# frankfurt_eth_pic.net
KiCad netlist of a schematic drawn in EAGLE
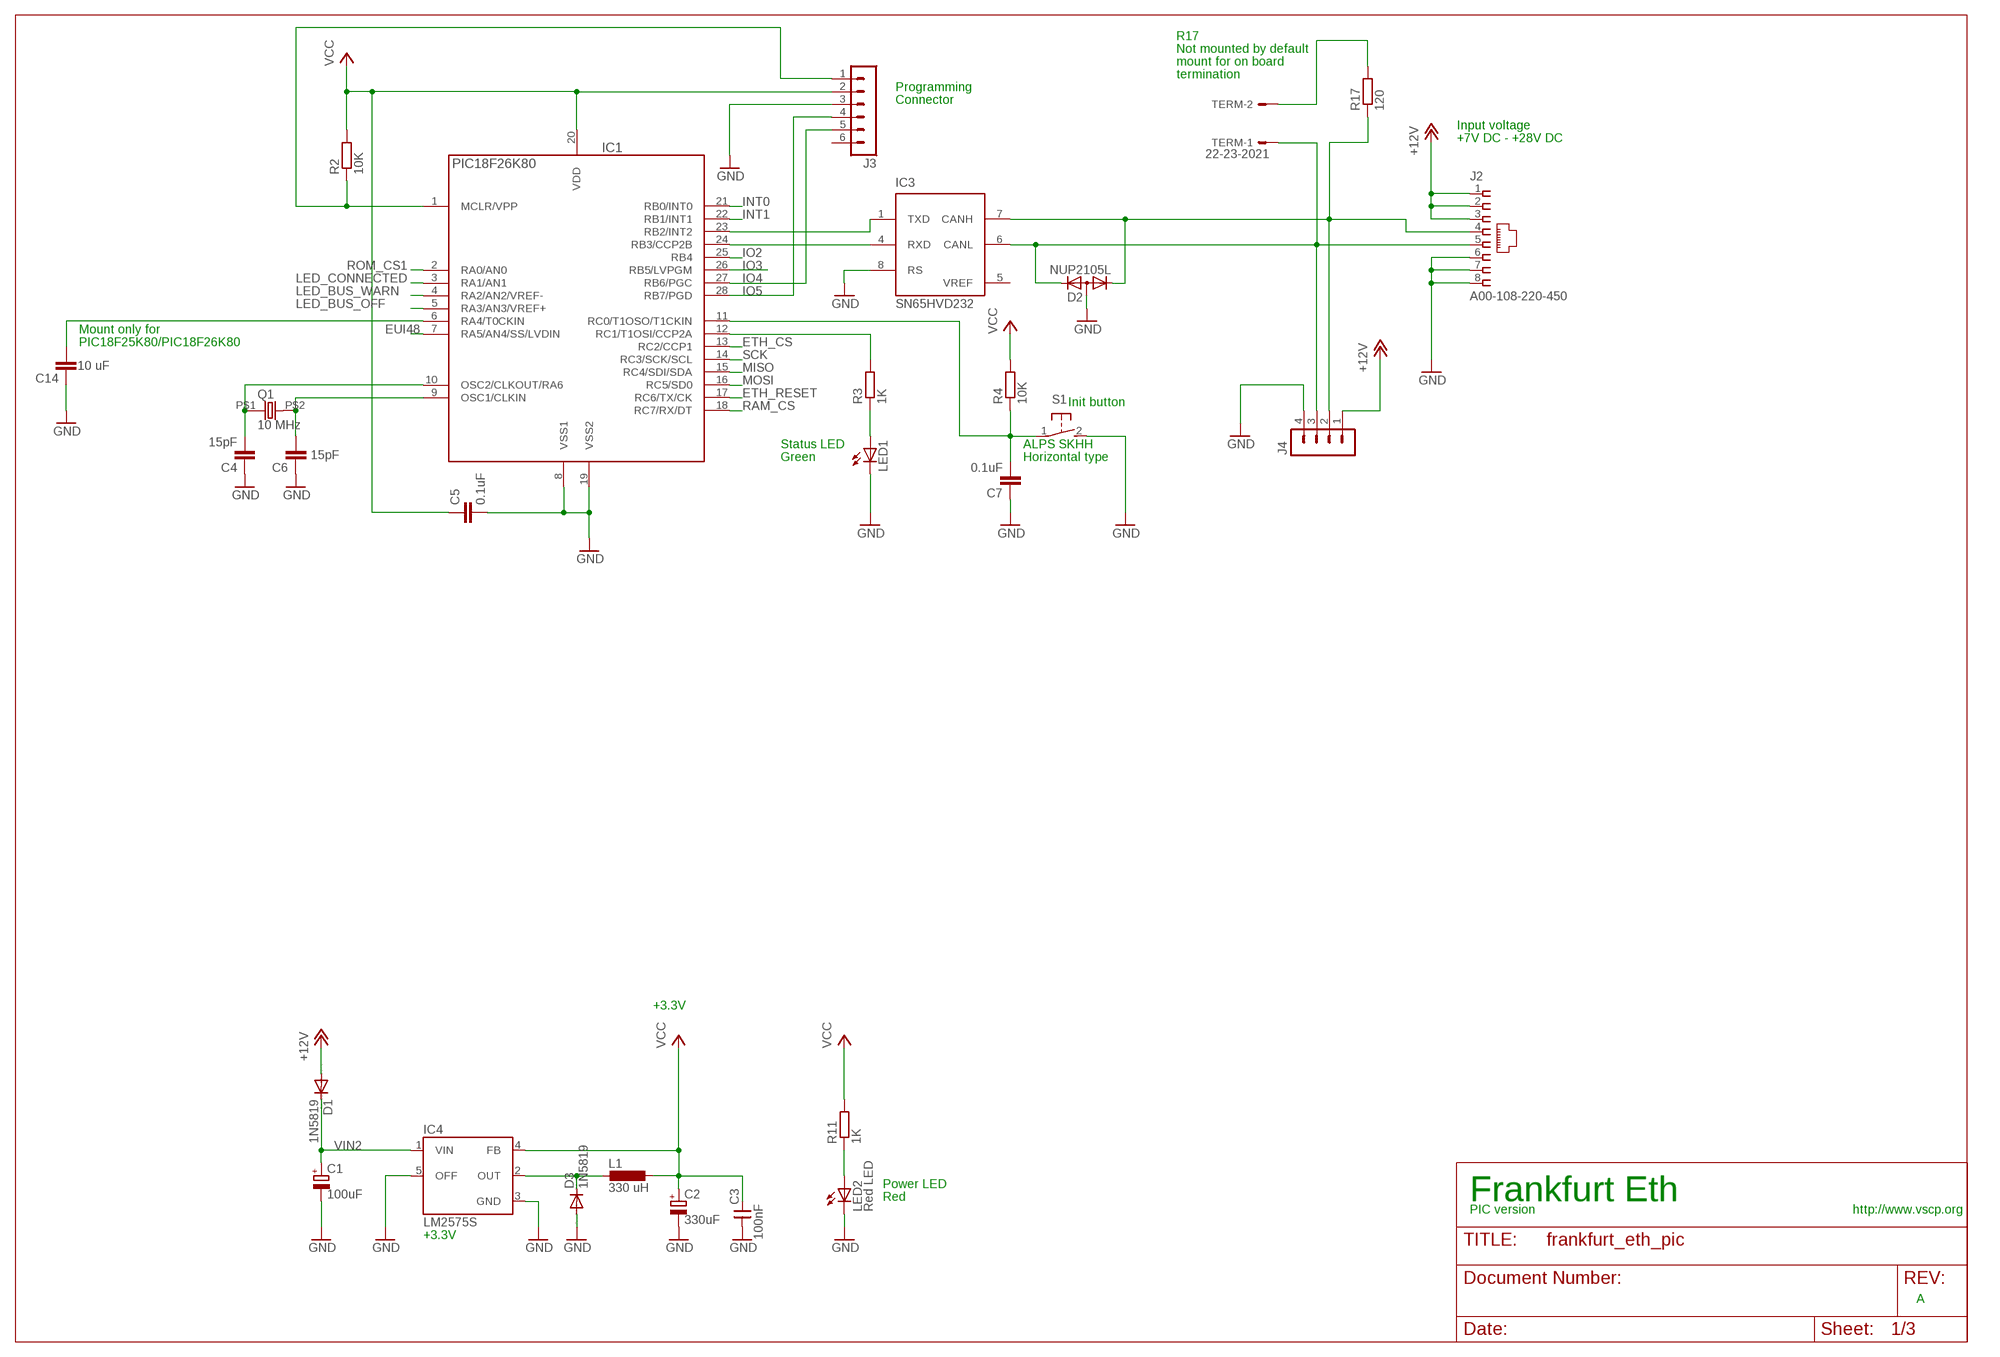
[diagram p0: schematic, sheet 1]
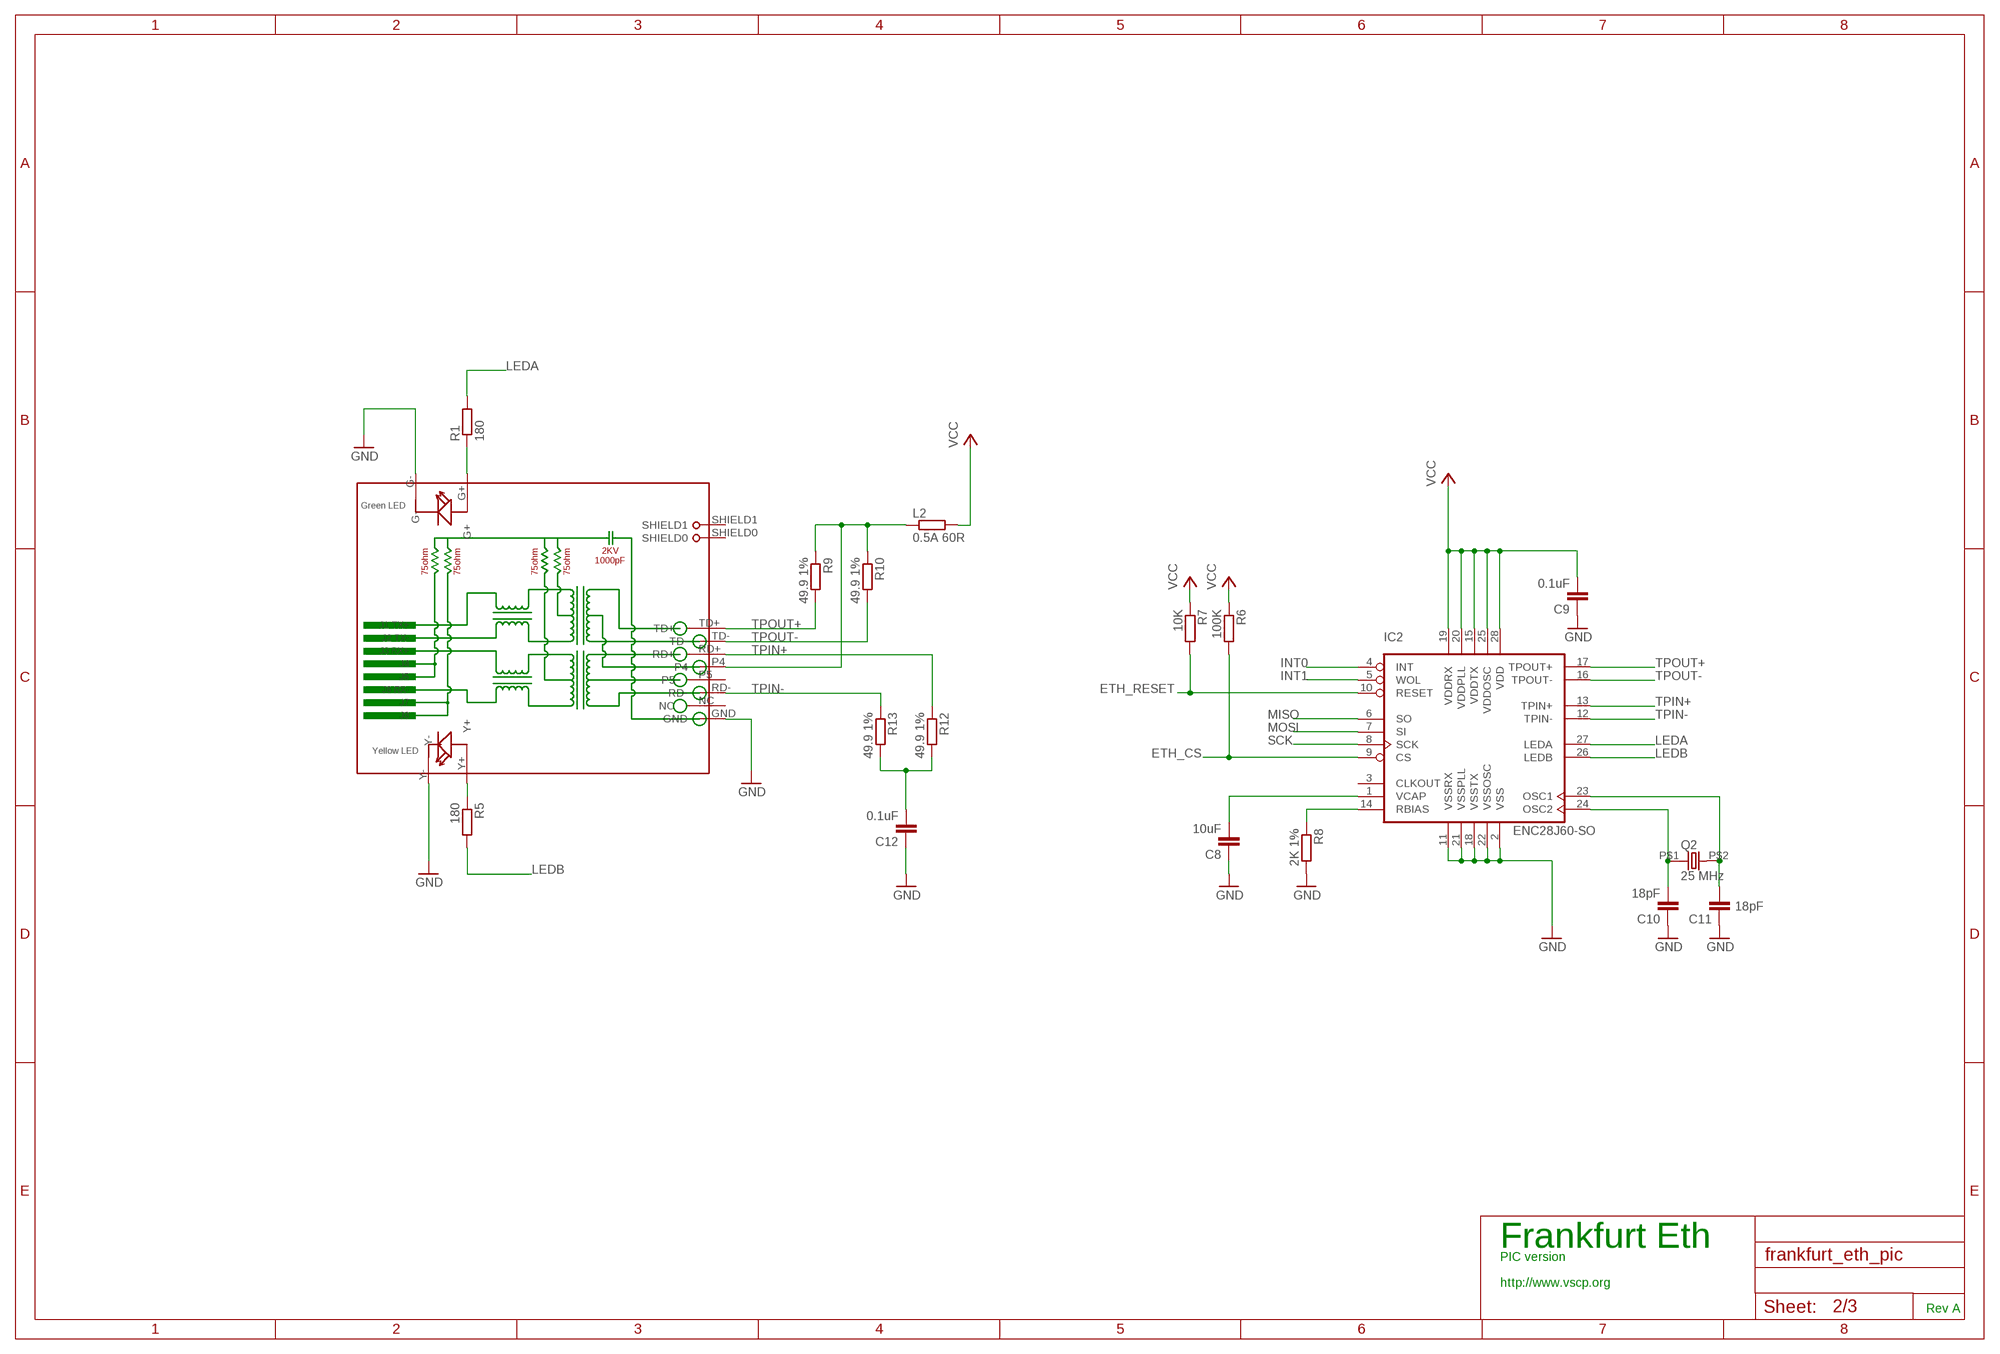
[diagram p1: schematic, sheet 2]
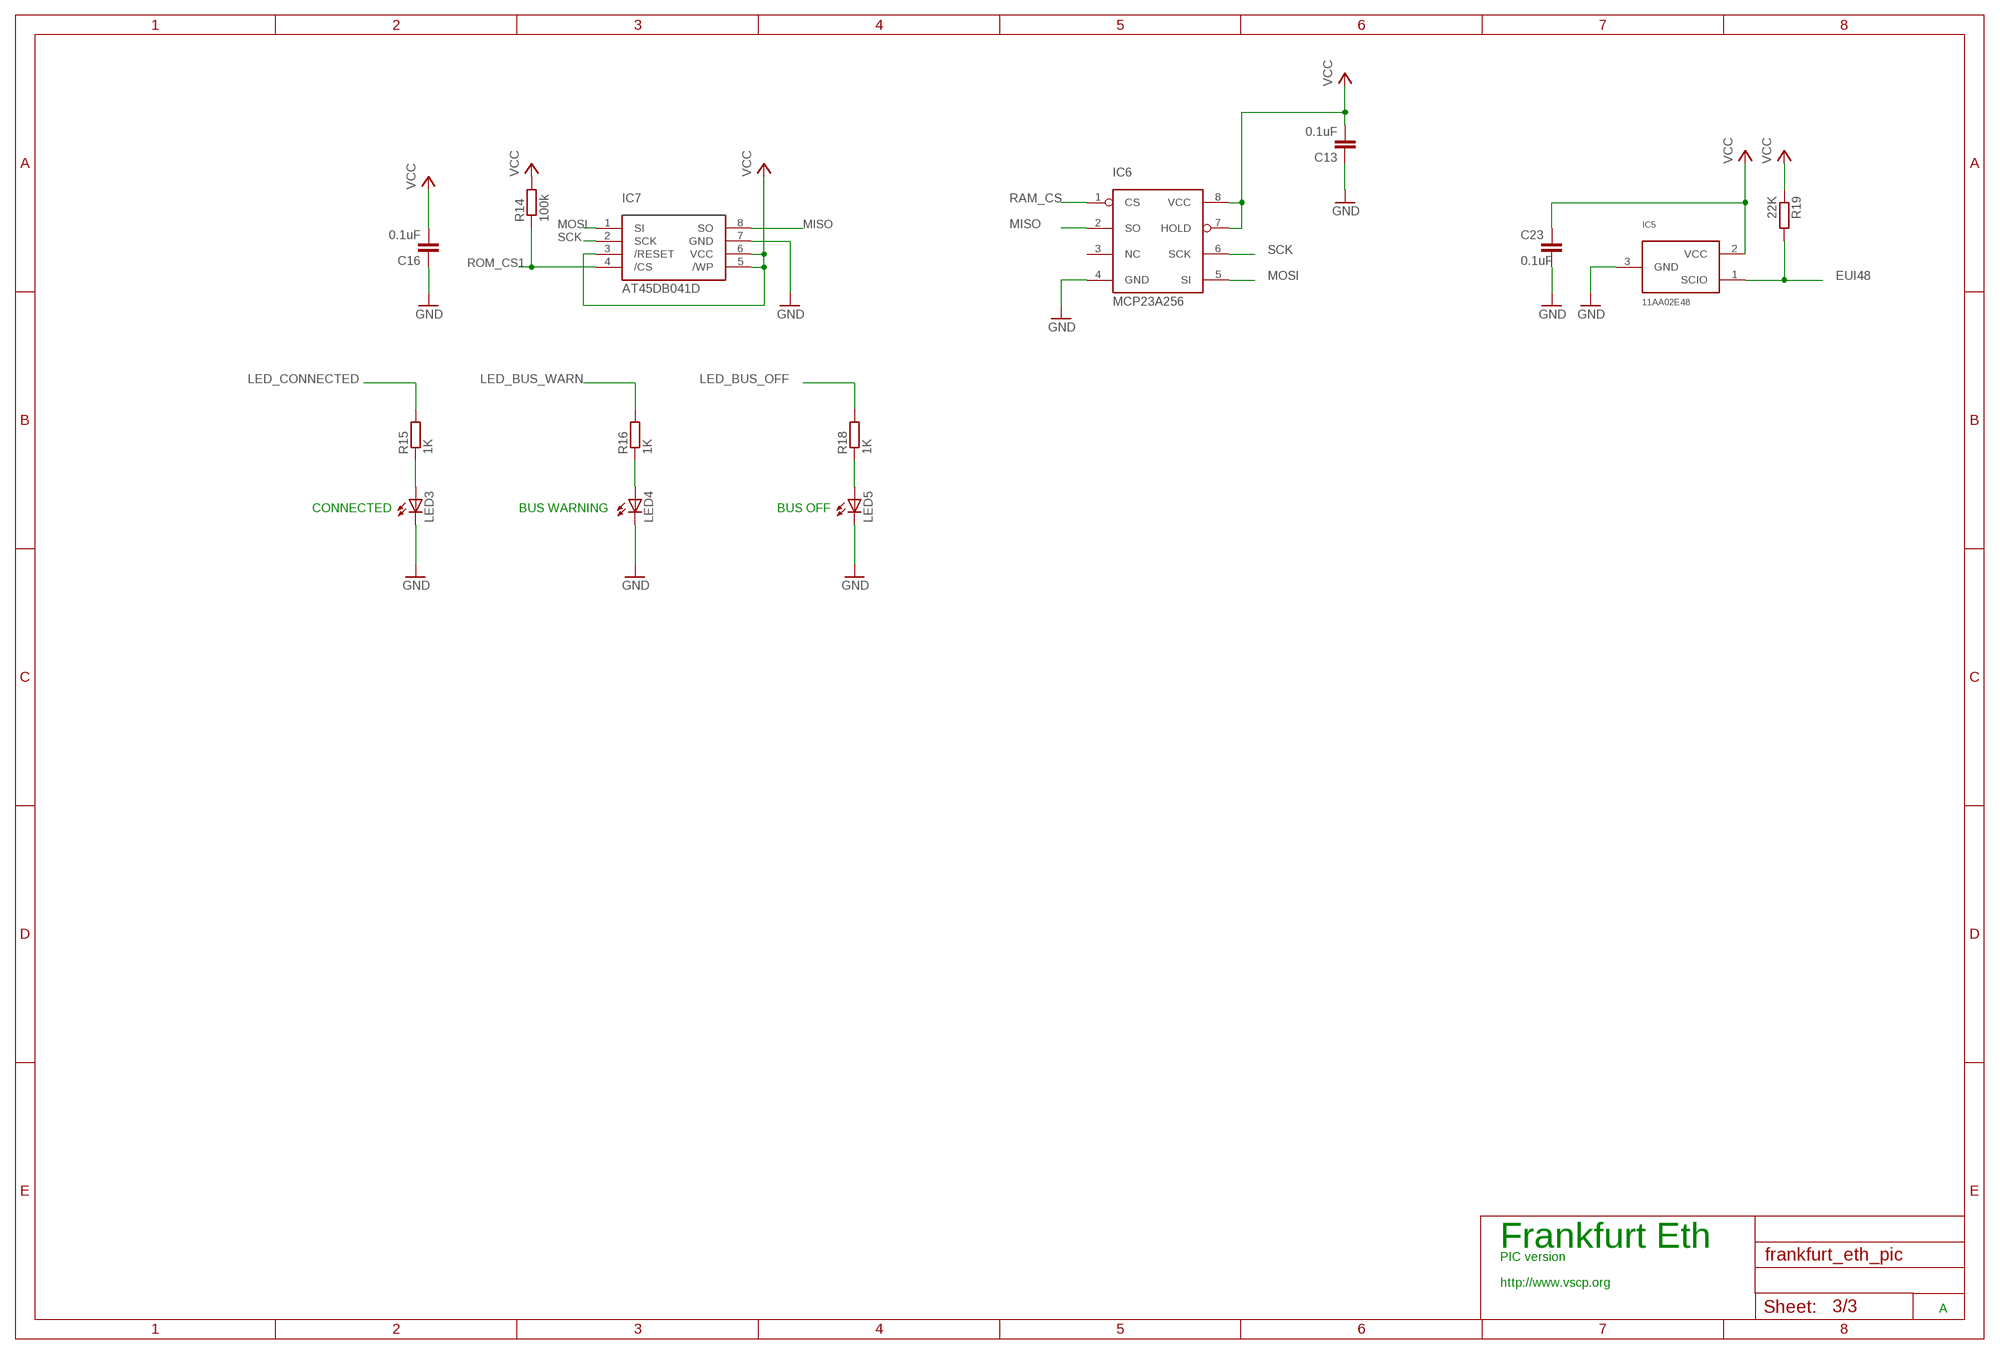
[diagram p2: schematic, sheet 3]

(export (version "E")
  (design (tool "Eeschema 10.0.6"))
  (components
    (comp (ref "C1")
      (value "100uF")
      (footprint "eagle-import:PANASONIC_D")
      (libsource (lib "eagle-import") (part "CPOL-EUD"))
    )
    (comp (ref "C2")
      (value "330uF")
      (footprint "eagle-import:PANASONIC_D")
      (libsource (lib "eagle-import") (part "CPOL-EUD"))
    )
    (comp (ref "C3")
      (value "100nF")
      (footprint "eagle-import:0805")
      (libsource (lib "eagle-import") (part "CNP-0805"))
    )
    (comp (ref "C4")
      (value "15pF")
      (footprint "eagle-import:C0805")
      (libsource (lib "eagle-import") (part "C-EUC0805"))
    )
    (comp (ref "C5")
      (value "0.1uF")
      (footprint "eagle-import:C0805")
      (libsource (lib "eagle-import") (part "C-EUC0805"))
    )
    (comp (ref "C6")
      (value "15pF")
      (footprint "eagle-import:C0805")
      (libsource (lib "eagle-import") (part "C-EUC0805"))
    )
    (comp (ref "C7")
      (value "0.1uF")
      (footprint "eagle-import:C0805")
      (libsource (lib "eagle-import") (part "C-EUC0805"))
    )
    (comp (ref "C14")
      (value "10 uF")
      (footprint "eagle-import:C0805")
      (libsource (lib "eagle-import") (part "C-EUC0805"))
    )
    (comp (ref "D1")
      (value "1N5819")
      (footprint "eagle-import:SOD123")
      (libsource (lib "eagle-import") (part "DIODE-SOD123"))
    )
    (comp (ref "D2")
      (value "NUP2105L")
      (footprint "eagle-import:SOT23")
      (libsource (lib "eagle-import") (part "DIODE-2CA|ACSOT23"))
    )
    (comp (ref "D3")
      (value "1N5819")
      (footprint "eagle-import:SOD123")
      (libsource (lib "eagle-import") (part "DIODE-SOD123"))
    )
    (comp (ref "IC1")
      (value "PIC18F26K80")
      (footprint "eagle-import:SO28")
      (libsource (lib "eagle-import") (part "PIC18F252-?I/SOL"))
    )
    (comp (ref "IC3")
      (value "SN65HVD232")
      (footprint "eagle-import:SO-08")
      (libsource (lib "eagle-import") (part "MCP2551SN"))
    )
    (comp (ref "IC4")
      (value "LM2575S")
      (footprint "eagle-import:TO263-5")
      (libsource (lib "eagle-import") (part "LM2575S"))
    )
    (comp (ref "J2")
      (value "A00-108-220-450")
      (footprint "eagle-import:RJ-45")
      (libsource (lib "eagle-import") (part "A00-108-220-450"))
    )
    (comp (ref "J3")
      (value "MA06-1")
      (footprint "eagle-import:MA06-1")
      (libsource (lib "eagle-import") (part "MA06-1"))
    )
    (comp (ref "J4")
      (value "MA04-1")
      (footprint "eagle-import:MA04-1")
      (libsource (lib "eagle-import") (part "MA04-1"))
    )
    (comp (ref "L1")
      (value "330 uH")
      (footprint "eagle-import:DO3316P")
      (libsource (lib "eagle-import") (part "DO3316P"))
    )
    (comp (ref "LED1")
      (value "LEDCHIP-LED0805")
      (footprint "eagle-import:CHIP-LED0805")
      (libsource (lib "eagle-import") (part "LEDCHIP-LED0805"))
    )
    (comp (ref "LED2")
      (value "Red LED")
      (footprint "eagle-import:CHIP-LED0805")
      (libsource (lib "eagle-import") (part "LEDCHIP-LED0805"))
    )
    (comp (ref "Q1")
      (value "10 MHz")
      (footprint "eagle-import:9C")
      (libsource (lib "eagle-import") (part "HC-49S"))
    )
    (comp (ref "R2")
      (value "10K")
      (footprint "eagle-import:R0805")
      (libsource (lib "eagle-import") (part "R-EU_R0805"))
    )
    (comp (ref "R3")
      (value "1K")
      (footprint "eagle-import:R0805")
      (libsource (lib "eagle-import") (part "R-EU_R0805"))
    )
    (comp (ref "R4")
      (value "10K")
      (footprint "eagle-import:R0805")
      (libsource (lib "eagle-import") (part "R-EU_R0805"))
    )
    (comp (ref "R11")
      (value "1K")
      (footprint "eagle-import:R0805")
      (libsource (lib "eagle-import") (part "R-EU_R0805"))
    )
    (comp (ref "R17")
      (value "120")
      (footprint "eagle-import:R0805")
      (libsource (lib "eagle-import") (part "R-EU_R0805"))
    )
    (comp (ref "S1")
      (value "31-XX")
      (footprint "eagle-import:B3F-31XX")
      (fields (field (name "MPN") "B3F-3100"))
      (libsource (lib "eagle-import") (part "31-XX"))
    )
    (comp (ref "TERM")
      (value "22-23-2021")
      (footprint "eagle-import:22-23-2021")
      (fields (field (name "MF") "MOLEX"))
      (libsource (lib "eagle-import") (part "22-23-2021"))
    )
    (comp (ref "C8")
      (value "10uF")
      (footprint "eagle-import:C0805")
      (libsource (lib "eagle-import") (part "C-EUC0805"))
    )
    (comp (ref "C9")
      (value "0.1uF")
      (footprint "eagle-import:C0805")
      (libsource (lib "eagle-import") (part "C-EUC0805"))
    )
    (comp (ref "C10")
      (value "18pF")
      (footprint "eagle-import:C0805")
      (libsource (lib "eagle-import") (part "C-EUC0805"))
    )
    (comp (ref "C11")
      (value "18pF")
      (footprint "eagle-import:C0805")
      (libsource (lib "eagle-import") (part "C-EUC0805"))
    )
    (comp (ref "C12")
      (value "0.1uF")
      (footprint "eagle-import:C0805")
      (libsource (lib "eagle-import") (part "C-EUC0805"))
    )
    (comp (ref "IC2")
      (value "ENC28J60-SO")
      (footprint "eagle-import:SO28W")
      (libsource (lib "eagle-import") (part "ENC28J60-SO"))
    )
    (comp (ref "L2")
      (value "0.5A 60R")
      (footprint "eagle-import:R0805")
      (libsource (lib "eagle-import") (part "R-EU_R0805"))
    )
    (comp (ref "Q2")
      (value "25 MHz")
      (footprint "eagle-import:9C")
      (libsource (lib "eagle-import") (part "HC-49S"))
    )
    (comp (ref "R1")
      (value "180")
      (footprint "eagle-import:R0805")
      (libsource (lib "eagle-import") (part "R-EU_R0805"))
    )
    (comp (ref "R5")
      (value "180")
      (footprint "eagle-import:R0805")
      (libsource (lib "eagle-import") (part "R-EU_R0805"))
    )
    (comp (ref "R6")
      (value "100K")
      (footprint "eagle-import:R0805")
      (libsource (lib "eagle-import") (part "R-EU_R0805"))
    )
    (comp (ref "R7")
      (value "10K")
      (footprint "eagle-import:R0805")
      (libsource (lib "eagle-import") (part "R-EU_R0805"))
    )
    (comp (ref "R8")
      (value "2K 1%")
      (footprint "eagle-import:R0805")
      (libsource (lib "eagle-import") (part "R-EU_R0805"))
    )
    (comp (ref "R9")
      (value "49.9 1%")
      (footprint "eagle-import:R0805")
      (libsource (lib "eagle-import") (part "R-EU_R0805"))
    )
    (comp (ref "R10")
      (value "49.9 1%")
      (footprint "eagle-import:R0805")
      (libsource (lib "eagle-import") (part "R-EU_R0805"))
    )
    (comp (ref "R12")
      (value "49.9 1%")
      (footprint "eagle-import:R0805")
      (libsource (lib "eagle-import") (part "R-EU_R0805"))
    )
    (comp (ref "R13")
      (value "49.9 1%")
      (footprint "eagle-import:R0805")
      (libsource (lib "eagle-import") (part "R-EU_R0805"))
    )
    (comp (ref "RJ1")
      (value "HR911105A")
      (footprint "eagle-import:HR911105A")
      (libsource (lib "eagle-import") (part "HR911105A"))
    )
    (comp (ref "C13")
      (value "0.1uF")
      (footprint "eagle-import:C0805")
      (libsource (lib "eagle-import") (part "C-EUC0805"))
    )
    (comp (ref "C16")
      (value "0.1uF")
      (footprint "eagle-import:C0805")
      (libsource (lib "eagle-import") (part "C-EUC0805"))
    )
    (comp (ref "C23")
      (value "0.1uF")
      (footprint "eagle-import:C0805")
      (libsource (lib "eagle-import") (part "C-EUC0805"))
    )
    (comp (ref "IC5")
      (value "11AA02E48")
      (footprint "eagle-import:SOT23")
      (libsource (lib "eagle-import") (part "11AA02E48"))
    )
    (comp (ref "IC6")
      (value "MCP23A256")
      (footprint "eagle-import:SO-8")
      (libsource (lib "eagle-import") (part "MCP23A256"))
    )
    (comp (ref "IC7")
      (value "AT45DB041D")
      (footprint "eagle-import:SOP8W")
      (libsource (lib "eagle-import") (part "AT45DB011DSOP8W"))
    )
    (comp (ref "LED3")
      (value "LEDCHIP-LED0805")
      (footprint "eagle-import:CHIP-LED0805")
      (libsource (lib "eagle-import") (part "LEDCHIP-LED0805"))
    )
    (comp (ref "LED4")
      (value "LEDCHIP-LED0805")
      (footprint "eagle-import:CHIP-LED0805")
      (libsource (lib "eagle-import") (part "LEDCHIP-LED0805"))
    )
    (comp (ref "LED5")
      (value "LEDCHIP-LED0805")
      (footprint "eagle-import:CHIP-LED0805")
      (libsource (lib "eagle-import") (part "LEDCHIP-LED0805"))
    )
    (comp (ref "R14")
      (value "100k")
      (footprint "eagle-import:M0805")
      (libsource (lib "eagle-import") (part "R-EU_M0805"))
    )
    (comp (ref "R15")
      (value "1K")
      (footprint "eagle-import:R0805")
      (libsource (lib "eagle-import") (part "R-EU_R0805"))
    )
    (comp (ref "R16")
      (value "1K")
      (footprint "eagle-import:R0805")
      (libsource (lib "eagle-import") (part "R-EU_R0805"))
    )
    (comp (ref "R18")
      (value "1K")
      (footprint "eagle-import:R0805")
      (libsource (lib "eagle-import") (part "R-EU_R0805"))
    )
    (comp (ref "R19")
      (value "22K")
      (footprint "eagle-import:M0805")
      (libsource (lib "eagle-import") (part "R-EU_M0805"))
    )
  )
  (nets
    (net (code "1") (name "+12V") (class "Default")
      (node (ref "D1") (pin "A") (pinfunction "A_A") (pintype "passive"))
      (node (ref "J2") (pin "1") (pinfunction "1_1") (pintype "passive"))
      (node (ref "J2") (pin "2") (pinfunction "2_2") (pintype "passive"))
      (node (ref "J2") (pin "3") (pinfunction "3_3") (pintype "passive"))
      (node (ref "J4") (pin "1") (pinfunction "1_1") (pintype "passive"))
    )
    (net (code "2") (name "ETH_CS") (class "Default")
      (node (ref "IC1") (pin "13") (pinfunction "RC2/CCP1_13") (pintype "bidirectional"))
      (node (ref "IC2") (pin "9") (pinfunction "CS_9") (pintype "input"))
      (node (ref "R6") (pin "2") (pinfunction "2_2") (pintype "passive"))
    )
    (net (code "3") (name "ETH_RESET") (class "Default")
      (node (ref "IC1") (pin "17") (pinfunction "RC6/TX/CK_17") (pintype "bidirectional"))
      (node (ref "IC2") (pin "10") (pinfunction "RESET_10") (pintype "input"))
      (node (ref "R7") (pin "2") (pinfunction "2_2") (pintype "passive"))
    )
    (net (code "4") (name "EUI48") (class "Default")
      (node (ref "IC1") (pin "7") (pinfunction "RA5/AN4/SS/LVDIN_7") (pintype "bidirectional"))
      (node (ref "IC5") (pin "1") (pinfunction "SCIO_1") (pintype "bidirectional"))
      (node (ref "R19") (pin "2") (pinfunction "2_2") (pintype "passive"))
    )
    (net (code "5") (name "GND") (class "Default")
      (node (ref "C1") (pin "-") (pinfunction "-_-") (pintype "passive"))
      (node (ref "C10") (pin "1") (pinfunction "1_1") (pintype "passive"))
      (node (ref "C11") (pin "1") (pinfunction "1_1") (pintype "passive"))
      (node (ref "C12") (pin "1") (pinfunction "1_1") (pintype "passive"))
      (node (ref "C13") (pin "1") (pinfunction "1_1") (pintype "passive"))
      (node (ref "C14") (pin "1") (pinfunction "1_1") (pintype "passive"))
      (node (ref "C16") (pin "1") (pinfunction "1_1") (pintype "passive"))
      (node (ref "C2") (pin "-") (pinfunction "-_-") (pintype "passive"))
      (node (ref "C23") (pin "2") (pinfunction "2_2") (pintype "passive"))
      (node (ref "C3") (pin "1") (pinfunction "1_1") (pintype "passive"))
      (node (ref "C4") (pin "1") (pinfunction "1_1") (pintype "passive"))
      (node (ref "C5") (pin "2") (pinfunction "2_2") (pintype "passive"))
      (node (ref "C6") (pin "1") (pinfunction "1_1") (pintype "passive"))
      (node (ref "C7") (pin "1") (pinfunction "1_1") (pintype "passive"))
      (node (ref "C8") (pin "1") (pinfunction "1_1") (pintype "passive"))
      (node (ref "C9") (pin "1") (pinfunction "1_1") (pintype "passive"))
      (node (ref "D2") (pin "3") (pinfunction "A_3") (pintype "passive"))
      (node (ref "D3") (pin "A") (pinfunction "A_A") (pintype "passive"))
      (node (ref "IC1") (pin "19") (pinfunction "VSS2_19") (pintype "power_in"))
      (node (ref "IC1") (pin "8") (pinfunction "VSS1_8") (pintype "power_in"))
      (node (ref "IC2") (pin "11") (pinfunction "VSSRX_11") (pintype "power_in"))
      (node (ref "IC2") (pin "18") (pinfunction "VSSTX_18") (pintype "power_in"))
      (node (ref "IC2") (pin "2") (pinfunction "VSS_2") (pintype "power_in"))
      (node (ref "IC2") (pin "21") (pinfunction "VSSPLL_21") (pintype "power_in"))
      (node (ref "IC2") (pin "22") (pinfunction "VSSOSC_22") (pintype "power_in"))
      (node (ref "IC3") (pin "8") (pinfunction "RS_8") (pintype "input"))
      (node (ref "IC4") (pin "3") (pinfunction "GND_3") (pintype "power_in"))
      (node (ref "IC4") (pin "5") (pinfunction "OFF_5") (pintype "input"))
      (node (ref "IC5") (pin "3") (pinfunction "GND_3") (pintype "power_in"))
      (node (ref "IC6") (pin "4") (pinfunction "GND_4") (pintype "power_in"))
      (node (ref "IC7") (pin "7") (pinfunction "GND_7") (pintype "power_in"))
      (node (ref "J2") (pin "6") (pinfunction "6_6") (pintype "passive"))
      (node (ref "J2") (pin "7") (pinfunction "7_7") (pintype "passive"))
      (node (ref "J2") (pin "8") (pinfunction "8_8") (pintype "passive"))
      (node (ref "J3") (pin "3") (pinfunction "3_3") (pintype "passive"))
      (node (ref "J4") (pin "4") (pinfunction "4_4") (pintype "passive"))
      (node (ref "LED1") (pin "C") (pinfunction "C_C") (pintype "passive"))
      (node (ref "LED2") (pin "C") (pinfunction "C_C") (pintype "passive"))
      (node (ref "LED3") (pin "C") (pinfunction "C_C") (pintype "passive"))
      (node (ref "LED4") (pin "C") (pinfunction "C_C") (pintype "passive"))
      (node (ref "LED5") (pin "C") (pinfunction "C_C") (pintype "passive"))
      (node (ref "R8") (pin "2") (pinfunction "2_2") (pintype "passive"))
      (node (ref "RJ1") (pin "G-") (pinfunction "G-_G-") (pintype "bidirectional"))
      (node (ref "RJ1") (pin "GND") (pinfunction "GND_GND") (pintype "bidirectional"))
      (node (ref "RJ1") (pin "Y-") (pinfunction "Y-_Y-") (pintype "bidirectional"))
      (node (ref "S1") (pin "2") (pinfunction "S_2") (pintype "passive"))
    )
    (net (code "6") (name "INT0") (class "Default")
      (node (ref "IC1") (pin "21") (pinfunction "RB0/INT0_21") (pintype "bidirectional"))
      (node (ref "IC2") (pin "4") (pinfunction "INT_4") (pintype "output"))
    )
    (net (code "7") (name "INT1") (class "Default")
      (node (ref "IC1") (pin "22") (pinfunction "RB1/INT1_22") (pintype "bidirectional"))
      (node (ref "IC2") (pin "5") (pinfunction "WOL_5") (pintype "output"))
    )
    (net (code "8") (name "IO2") (class "Default")
      (node (ref "IC1") (pin "25") (pinfunction "RB4_25") (pintype "bidirectional"))
    )
    (net (code "9") (name "IO3") (class "Default")
      (node (ref "IC1") (pin "26") (pinfunction "RB5/LVPGM_26") (pintype "bidirectional"))
    )
    (net (code "10") (name "IO4") (class "Default")
      (node (ref "IC1") (pin "27") (pinfunction "RB6/PGC_27") (pintype "bidirectional"))
      (node (ref "J3") (pin "5") (pinfunction "5_5") (pintype "passive"))
    )
    (net (code "11") (name "IO5") (class "Default")
      (node (ref "IC1") (pin "28") (pinfunction "RB7/PGD_28") (pintype "bidirectional"))
      (node (ref "J3") (pin "4") (pinfunction "4_4") (pintype "passive"))
    )
    (net (code "12") (name "LEDA") (class "Default")
      (node (ref "IC2") (pin "27") (pinfunction "LEDA_27") (pintype "output"))
      (node (ref "R1") (pin "2") (pinfunction "2_2") (pintype "passive"))
    )
    (net (code "13") (name "LEDB") (class "Default")
      (node (ref "IC2") (pin "26") (pinfunction "LEDB_26") (pintype "output"))
      (node (ref "R5") (pin "2") (pinfunction "2_2") (pintype "passive"))
    )
    (net (code "14") (name "LED_BUS_OFF") (class "Default")
      (node (ref "IC1") (pin "5") (pinfunction "RA3/AN3/VREF+_5") (pintype "bidirectional"))
      (node (ref "R18") (pin "2") (pinfunction "2_2") (pintype "passive"))
    )
    (net (code "15") (name "LED_BUS_WARN") (class "Default")
      (node (ref "IC1") (pin "4") (pinfunction "RA2/AN2/VREF-_4") (pintype "bidirectional"))
      (node (ref "R16") (pin "2") (pinfunction "2_2") (pintype "passive"))
    )
    (net (code "16") (name "LED_CONNECTED") (class "Default")
      (node (ref "IC1") (pin "3") (pinfunction "RA1/AN1_3") (pintype "bidirectional"))
      (node (ref "R15") (pin "2") (pinfunction "2_2") (pintype "passive"))
    )
    (net (code "17") (name "MISO") (class "Default")
      (node (ref "IC1") (pin "15") (pinfunction "RC4/SDI/SDA_15") (pintype "bidirectional"))
      (node (ref "IC2") (pin "6") (pinfunction "SO_6") (pintype "output"))
      (node (ref "IC6") (pin "2") (pinfunction "SO_2") (pintype "output"))
      (node (ref "IC7") (pin "8") (pinfunction "SO_8") (pintype "output"))
    )
    (net (code "18") (name "MOSI") (class "Default")
      (node (ref "IC1") (pin "16") (pinfunction "RC5/SD0_16") (pintype "bidirectional"))
      (node (ref "IC2") (pin "7") (pinfunction "SI_7") (pintype "input"))
      (node (ref "IC6") (pin "5") (pinfunction "SI_5") (pintype "input"))
      (node (ref "IC7") (pin "1") (pinfunction "SI_1") (pintype "input"))
    )
    (net (code "19") (name "Net-(C12-Pad2)") (class "Default")
      (node (ref "C12") (pin "2") (pinfunction "2_2") (pintype "passive"))
      (node (ref "R12") (pin "2") (pinfunction "2_2") (pintype "passive"))
      (node (ref "R13") (pin "2") (pinfunction "2_2") (pintype "passive"))
    )
    (net (code "20") (name "Net-(D2-K1)") (class "Default")
      (node (ref "D2") (pin "1") (pinfunction "K1_1") (pintype "passive"))
      (node (ref "IC3") (pin "7") (pinfunction "CANH_7") (pintype "bidirectional"))
      (node (ref "J2") (pin "4") (pinfunction "4_4") (pintype "passive"))
      (node (ref "J4") (pin "2") (pinfunction "2_2") (pintype "passive"))
      (node (ref "R17") (pin "1") (pinfunction "1_1") (pintype "passive"))
    )
    (net (code "21") (name "Net-(D2-K2)") (class "Default")
      (node (ref "D2") (pin "2") (pinfunction "K2_2") (pintype "passive"))
      (node (ref "IC3") (pin "6") (pinfunction "CANL_6") (pintype "bidirectional"))
      (node (ref "J2") (pin "5") (pinfunction "5_5") (pintype "passive"))
      (node (ref "J4") (pin "3") (pinfunction "3_3") (pintype "passive"))
      (node (ref "TERM") (pin "1") (pinfunction "S_1") (pintype "passive"))
    )
    (net (code "22") (name "Net-(IC1-MCLR{slash}VPP)") (class "Default")
      (node (ref "IC1") (pin "1") (pinfunction "MCLR/VPP_1") (pintype "input"))
      (node (ref "J3") (pin "1") (pinfunction "1_1") (pintype "passive"))
      (node (ref "R2") (pin "1") (pinfunction "1_1") (pintype "passive"))
    )
    (net (code "23") (name "Net-(IC1-OSC1{slash}CLKIN)") (class "Default")
      (node (ref "C6") (pin "2") (pinfunction "2_2") (pintype "passive"))
      (node (ref "IC1") (pin "9") (pinfunction "OSC1/CLKIN_9") (pintype "input"))
      (node (ref "Q1") (pin "P$2") (pinfunction "2_P$2") (pintype "passive"))
    )
    (net (code "24") (name "Net-(IC1-OSC2{slash}CLKOUT{slash}RA6)") (class "Default")
      (node (ref "C4") (pin "2") (pinfunction "2_2") (pintype "passive"))
      (node (ref "IC1") (pin "10") (pinfunction "OSC2/CLKOUT/RA6_10") (pintype "output"))
      (node (ref "Q1") (pin "P$1") (pinfunction "1_P$1") (pintype "passive"))
    )
    (net (code "25") (name "Net-(IC1-RA4{slash}T0CKIN)") (class "Default")
      (node (ref "C14") (pin "2") (pinfunction "2_2") (pintype "passive"))
      (node (ref "IC1") (pin "6") (pinfunction "RA4/T0CKIN_6") (pintype "open_collector"))
    )
    (net (code "26") (name "Net-(IC1-RB2{slash}INT2)") (class "Default")
      (node (ref "IC1") (pin "23") (pinfunction "RB2/INT2_23") (pintype "bidirectional"))
      (node (ref "IC3") (pin "1") (pinfunction "TXD_1") (pintype "input"))
    )
    (net (code "27") (name "Net-(IC1-RB3{slash}CCP2B)") (class "Default")
      (node (ref "IC1") (pin "24") (pinfunction "RB3/CCP2B_24") (pintype "bidirectional"))
      (node (ref "IC3") (pin "4") (pinfunction "RXD_4") (pintype "output"))
    )
    (net (code "28") (name "Net-(IC1-RC0{slash}T1OSO{slash}T1CKIN)") (class "Default")
      (node (ref "C7") (pin "2") (pinfunction "2_2") (pintype "passive"))
      (node (ref "IC1") (pin "11") (pinfunction "RC0/T1OSO/T1CKIN_11") (pintype "bidirectional"))
      (node (ref "R4") (pin "1") (pinfunction "1_1") (pintype "passive"))
      (node (ref "S1") (pin "1") (pinfunction "P_1") (pintype "passive"))
    )
    (net (code "29") (name "Net-(IC1-RC1{slash}T1OSI{slash}CCP2A)") (class "Default")
      (node (ref "IC1") (pin "12") (pinfunction "RC1/T1OSI/CCP2A_12") (pintype "bidirectional"))
      (node (ref "R3") (pin "2") (pinfunction "2_2") (pintype "passive"))
    )
    (net (code "30") (name "Net-(IC2-OSC1)") (class "Default")
      (node (ref "C11") (pin "2") (pinfunction "2_2") (pintype "passive"))
      (node (ref "IC2") (pin "23") (pinfunction "OSC1_23") (pintype "input"))
      (node (ref "Q2") (pin "P$2") (pinfunction "2_P$2") (pintype "passive"))
    )
    (net (code "31") (name "Net-(IC2-OSC2)") (class "Default")
      (node (ref "C10") (pin "2") (pinfunction "2_2") (pintype "passive"))
      (node (ref "IC2") (pin "24") (pinfunction "OSC2_24") (pintype "output"))
      (node (ref "Q2") (pin "P$1") (pinfunction "1_P$1") (pintype "passive"))
    )
    (net (code "32") (name "Net-(IC2-RBIAS)") (class "Default")
      (node (ref "IC2") (pin "14") (pinfunction "RBIAS_14") (pintype "passive"))
      (node (ref "R8") (pin "1") (pinfunction "1_1") (pintype "passive"))
    )
    (net (code "33") (name "Net-(IC2-VCAP)") (class "Default")
      (node (ref "C8") (pin "2") (pinfunction "2_2") (pintype "passive"))
      (node (ref "IC2") (pin "1") (pinfunction "VCAP_1") (pintype "power_in"))
    )
    (net (code "34") (name "Net-(IC4-OUT)") (class "Default")
      (node (ref "D3") (pin "C") (pinfunction "C_C") (pintype "passive"))
      (node (ref "IC4") (pin "2") (pinfunction "OUT_2") (pintype "output"))
      (node (ref "L1") (pin "1") (pinfunction "1_1") (pintype "passive"))
    )
    (net (code "35") (name "Net-(L2-Pad1)") (class "Default")
      (node (ref "L2") (pin "1") (pinfunction "1_1") (pintype "passive"))
      (node (ref "R10") (pin "1") (pinfunction "1_1") (pintype "passive"))
      (node (ref "R9") (pin "1") (pinfunction "1_1") (pintype "passive"))
      (node (ref "RJ1") (pin "P4") (pinfunction "P4_P4") (pintype "bidirectional"))
    )
    (net (code "36") (name "Net-(LED1-PadA)") (class "Default")
      (node (ref "LED1") (pin "A") (pinfunction "A_A") (pintype "passive"))
      (node (ref "R3") (pin "1") (pinfunction "1_1") (pintype "passive"))
    )
    (net (code "37") (name "Net-(LED2-PadA)") (class "Default")
      (node (ref "LED2") (pin "A") (pinfunction "A_A") (pintype "passive"))
      (node (ref "R11") (pin "1") (pinfunction "1_1") (pintype "passive"))
    )
    (net (code "38") (name "Net-(LED3-PadA)") (class "Default")
      (node (ref "LED3") (pin "A") (pinfunction "A_A") (pintype "passive"))
      (node (ref "R15") (pin "1") (pinfunction "1_1") (pintype "passive"))
    )
    (net (code "39") (name "Net-(LED4-PadA)") (class "Default")
      (node (ref "LED4") (pin "A") (pinfunction "A_A") (pintype "passive"))
      (node (ref "R16") (pin "1") (pinfunction "1_1") (pintype "passive"))
    )
    (net (code "40") (name "Net-(LED5-PadA)") (class "Default")
      (node (ref "LED5") (pin "A") (pinfunction "A_A") (pintype "passive"))
      (node (ref "R18") (pin "1") (pinfunction "1_1") (pintype "passive"))
    )
    (net (code "41") (name "Net-(R1-Pad1)") (class "Default")
      (node (ref "R1") (pin "1") (pinfunction "1_1") (pintype "passive"))
      (node (ref "RJ1") (pin "G+") (pinfunction "G+_G+") (pintype "bidirectional"))
    )
    (net (code "42") (name "Net-(R5-Pad1)") (class "Default")
      (node (ref "R5") (pin "1") (pinfunction "1_1") (pintype "passive"))
      (node (ref "RJ1") (pin "Y+") (pinfunction "Y+_Y+") (pintype "bidirectional"))
    )
    (net (code "43") (name "Net-(TERMB-S)") (class "Default")
      (node (ref "R17") (pin "2") (pinfunction "2_2") (pintype "passive"))
      (node (ref "TERM") (pin "2") (pinfunction "S_2") (pintype "passive"))
    )
    (net (code "44") (name "RAM_CS") (class "Default")
      (node (ref "IC1") (pin "18") (pinfunction "RC7/RX/DT_18") (pintype "bidirectional"))
      (node (ref "IC6") (pin "1") (pinfunction "CS_1") (pintype "input"))
    )
    (net (code "45") (name "ROM_CS1") (class "Default")
      (node (ref "IC1") (pin "2") (pinfunction "RA0/AN0_2") (pintype "bidirectional"))
      (node (ref "IC7") (pin "4") (pinfunction "/CS_4") (pintype "input"))
      (node (ref "R14") (pin "1") (pinfunction "1_1") (pintype "passive"))
    )
    (net (code "46") (name "SCK") (class "Default")
      (node (ref "IC1") (pin "14") (pinfunction "RC3/SCK/SCL_14") (pintype "bidirectional"))
      (node (ref "IC2") (pin "8") (pinfunction "SCK_8") (pintype "input"))
      (node (ref "IC6") (pin "6") (pinfunction "SCK_6") (pintype "input"))
      (node (ref "IC7") (pin "2") (pinfunction "SCK_2") (pintype "input"))
    )
    (net (code "47") (name "TPIN+") (class "Default")
      (node (ref "IC2") (pin "13") (pinfunction "TPIN+_13") (pintype "input"))
      (node (ref "R12") (pin "1") (pinfunction "1_1") (pintype "passive"))
      (node (ref "RJ1") (pin "RD+") (pinfunction "RD+_RD+") (pintype "bidirectional"))
    )
    (net (code "48") (name "TPIN-") (class "Default")
      (node (ref "IC2") (pin "12") (pinfunction "TPIN-_12") (pintype "input"))
      (node (ref "R13") (pin "1") (pinfunction "1_1") (pintype "passive"))
      (node (ref "RJ1") (pin "RD-") (pinfunction "RD-_RD-") (pintype "bidirectional"))
    )
    (net (code "49") (name "TPOUT+") (class "Default")
      (node (ref "IC2") (pin "17") (pinfunction "TPOUT+_17") (pintype "output"))
      (node (ref "R9") (pin "2") (pinfunction "2_2") (pintype "passive"))
      (node (ref "RJ1") (pin "TD+") (pinfunction "TD+_TD+") (pintype "bidirectional"))
    )
    (net (code "50") (name "TPOUT-") (class "Default")
      (node (ref "IC2") (pin "16") (pinfunction "TPOUT-_16") (pintype "output"))
      (node (ref "R10") (pin "2") (pinfunction "2_2") (pintype "passive"))
      (node (ref "RJ1") (pin "TD-") (pinfunction "TD-_TD-") (pintype "bidirectional"))
    )
    (net (code "51") (name "VCC") (class "Default")
      (node (ref "C13") (pin "2") (pinfunction "2_2") (pintype "passive"))
      (node (ref "C16") (pin "2") (pinfunction "2_2") (pintype "passive"))
      (node (ref "C2") (pin "+") (pinfunction "+_+") (pintype "passive"))
      (node (ref "C23") (pin "1") (pinfunction "1_1") (pintype "passive"))
      (node (ref "C3") (pin "2") (pinfunction "2_2") (pintype "passive"))
      (node (ref "C5") (pin "1") (pinfunction "1_1") (pintype "passive"))
      (node (ref "C9") (pin "2") (pinfunction "2_2") (pintype "passive"))
      (node (ref "IC1") (pin "20") (pinfunction "VDD_20") (pintype "power_in"))
      (node (ref "IC2") (pin "15") (pinfunction "VDDTX_15") (pintype "power_in"))
      (node (ref "IC2") (pin "19") (pinfunction "VDDRX_19") (pintype "power_in"))
      (node (ref "IC2") (pin "20") (pinfunction "VDDPLL_20") (pintype "power_in"))
      (node (ref "IC2") (pin "25") (pinfunction "VDDOSC_25") (pintype "power_in"))
      (node (ref "IC2") (pin "28") (pinfunction "VDD_28") (pintype "power_in"))
      (node (ref "IC4") (pin "4") (pinfunction "FB_4") (pintype "input"))
      (node (ref "IC5") (pin "2") (pinfunction "VCC_2") (pintype "power_in"))
      (node (ref "IC6") (pin "7") (pinfunction "HOLD_7") (pintype "input"))
      (node (ref "IC6") (pin "8") (pinfunction "VCC_8") (pintype "power_in"))
      (node (ref "IC7") (pin "3") (pinfunction "/RESET_3") (pintype "input"))
      (node (ref "IC7") (pin "5") (pinfunction "/WP_5") (pintype "input"))
      (node (ref "IC7") (pin "6") (pinfunction "VCC_6") (pintype "power_in"))
      (node (ref "J3") (pin "2") (pinfunction "2_2") (pintype "passive"))
      (node (ref "L1") (pin "2") (pinfunction "2_2") (pintype "passive"))
      (node (ref "L2") (pin "2") (pinfunction "2_2") (pintype "passive"))
      (node (ref "R11") (pin "2") (pinfunction "2_2") (pintype "passive"))
      (node (ref "R14") (pin "2") (pinfunction "2_2") (pintype "passive"))
      (node (ref "R19") (pin "1") (pinfunction "1_1") (pintype "passive"))
      (node (ref "R2") (pin "2") (pinfunction "2_2") (pintype "passive"))
      (node (ref "R4") (pin "2") (pinfunction "2_2") (pintype "passive"))
      (node (ref "R6") (pin "1") (pinfunction "1_1") (pintype "passive"))
      (node (ref "R7") (pin "1") (pinfunction "1_1") (pintype "passive"))
    )
    (net (code "52") (name "VIN2") (class "Default")
      (node (ref "C1") (pin "+") (pinfunction "+_+") (pintype "passive"))
      (node (ref "D1") (pin "C") (pinfunction "C_C") (pintype "passive"))
      (node (ref "IC4") (pin "1") (pinfunction "VIN_1") (pintype "power_in"))
    )
    (net (code "53") (name "VREF") (class "Default")
      (node (ref "IC3") (pin "5") (pinfunction "VREF_5") (pintype "power_in"))
    )
    (net (code "54") (name "unconnected-(IC2-CLKOUT-Pad3)") (class "Default")
      (node (ref "IC2") (pin "3") (pinfunction "CLKOUT_3") (pintype "output"))
    )
    (net (code "55") (name "unconnected-(IC6-NC-Pad3)") (class "Default")
      (node (ref "IC6") (pin "3") (pinfunction "NC_3") (pintype "no_connect"))
    )
    (net (code "56") (name "unconnected-(J3-Pad6)") (class "Default")
      (node (ref "J3") (pin "6") (pinfunction "6_6") (pintype "passive"))
    )
    (net (code "57") (name "unconnected-(RJ1-PadNC)") (class "Default")
      (node (ref "RJ1") (pin "NC") (pinfunction "NC_NC") (pintype "bidirectional"))
    )
    (net (code "58") (name "unconnected-(RJ1-PadP5)") (class "Default")
      (node (ref "RJ1") (pin "P5") (pinfunction "P5_P5") (pintype "bidirectional"))
    )
    (net (code "59") (name "unconnected-(RJ1-PadSHIELD0)") (class "Default")
      (node (ref "RJ1") (pin "SHIELD0") (pinfunction "SHIELD0_SHIELD0") (pintype "bidirectional"))
    )
    (net (code "60") (name "unconnected-(RJ1-PadSHIELD1)") (class "Default")
      (node (ref "RJ1") (pin "SHIELD1") (pinfunction "SHIELD1_SHIELD1") (pintype "bidirectional"))
    )
  )
)
